# Weather_Shield_V12.net
KiCad netlist of a schematic drawn in EAGLE
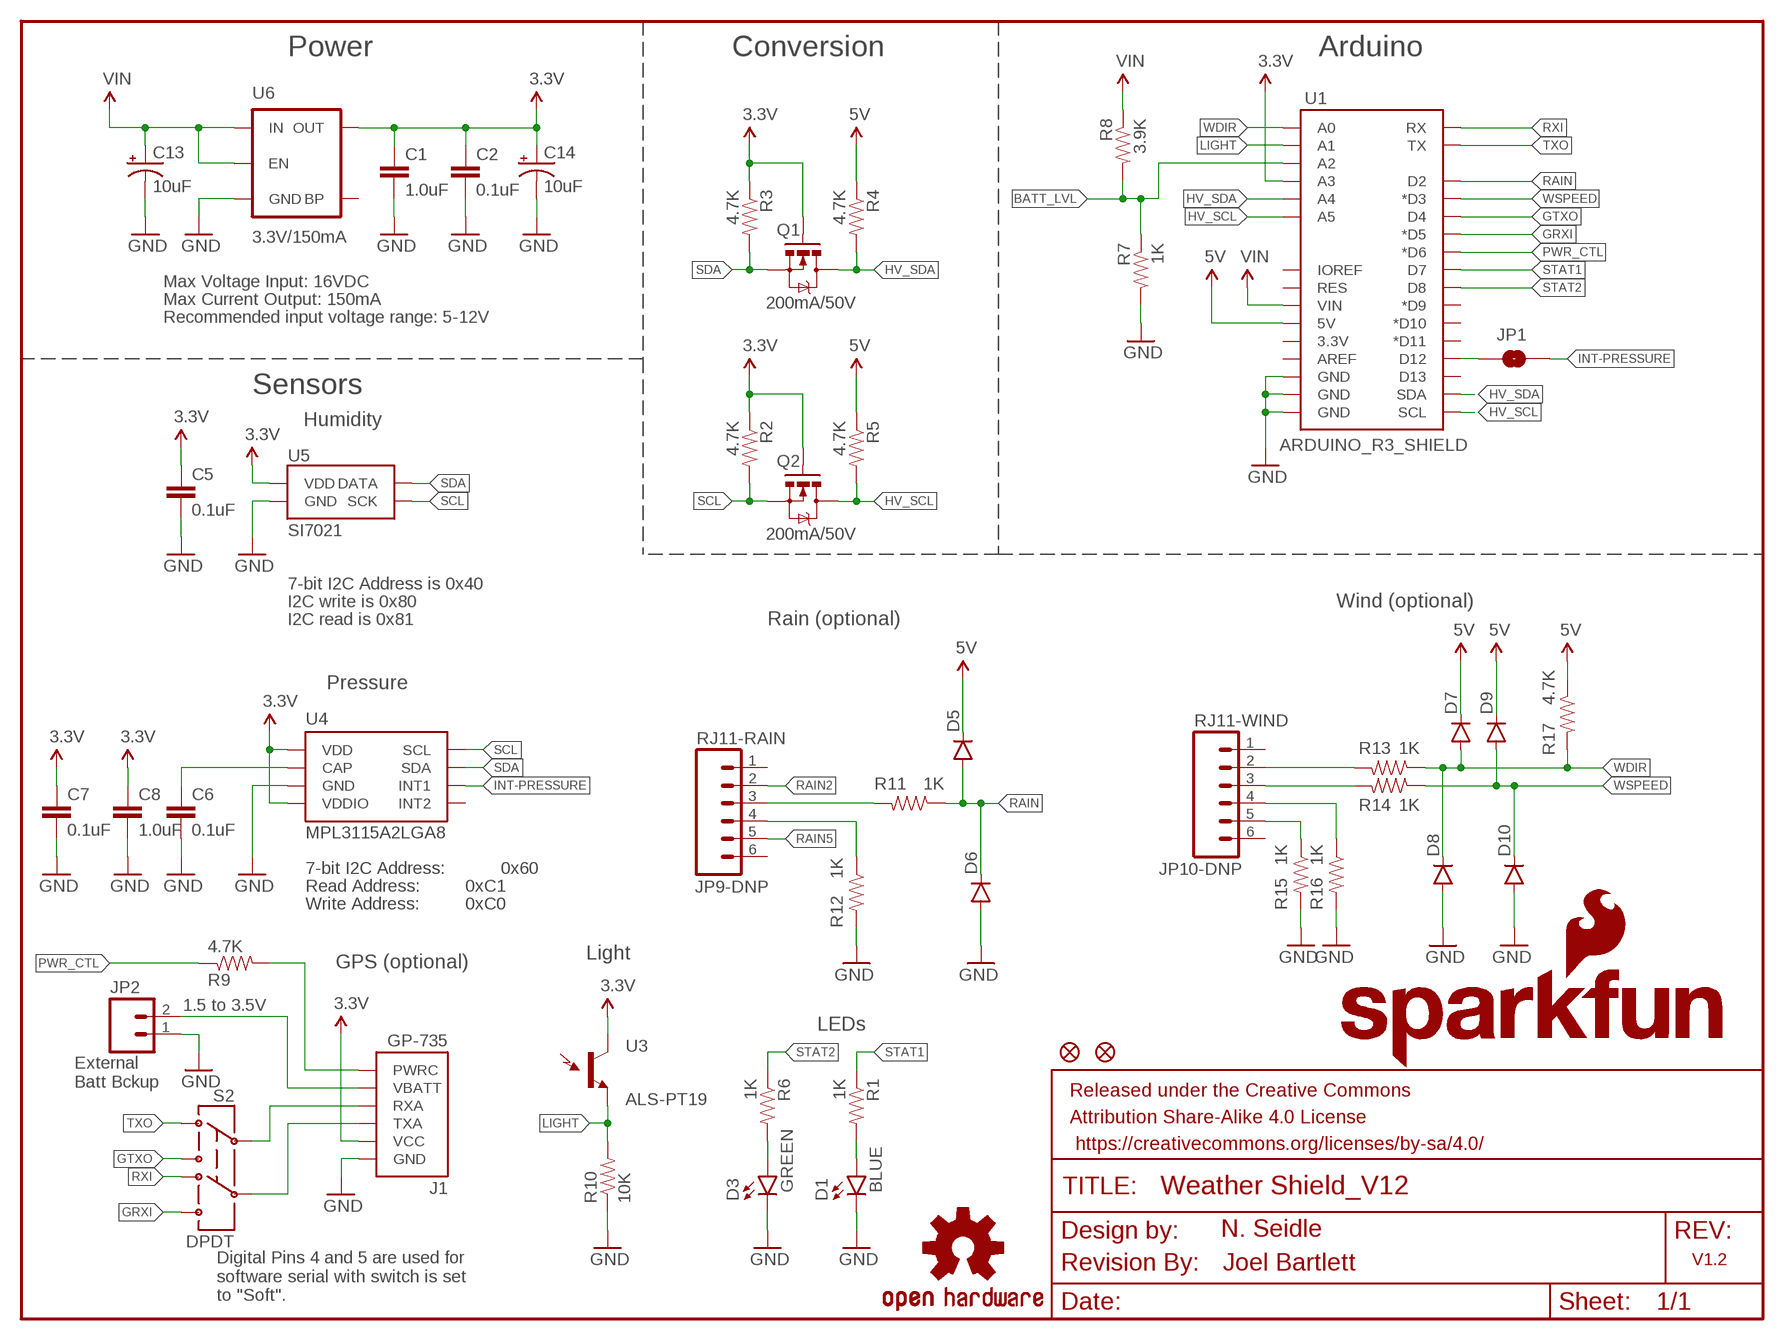
[diagram p0: schematic, sheet 1]

(export (version "E")
  (design (tool "Eeschema 10.0.6"))
  (components
    (comp (ref "C1")
      (value "1.0uF")
      (footprint "eagle-import:0603-CAP")
      (libsource (lib "eagle-import") (part "1.0UF-16V-10%(0603)"))
    )
    (comp (ref "C2")
      (value "0.1uF")
      (footprint "eagle-import:0603-CAP")
      (libsource (lib "eagle-import") (part "0.1UF-25V(+80/-20%)(0603)"))
    )
    (comp (ref "C5")
      (value "0.1uF")
      (footprint "eagle-import:0603-CAP")
      (libsource (lib "eagle-import") (part "0.1UF-25V(+80/-20%)(0603)"))
    )
    (comp (ref "C6")
      (value "0.1uF")
      (footprint "eagle-import:0603-CAP")
      (libsource (lib "eagle-import") (part "0.1UF-25V(+80/-20%)(0603)"))
    )
    (comp (ref "C7")
      (value "0.1uF")
      (footprint "eagle-import:0603-CAP")
      (libsource (lib "eagle-import") (part "0.1UF-25V(+80/-20%)(0603)"))
    )
    (comp (ref "C8")
      (value "1.0uF")
      (footprint "eagle-import:0603-CAP")
      (libsource (lib "eagle-import") (part "1.0UF-16V-10%(0603)"))
    )
    (comp (ref "C13")
      (value "10uF")
      (footprint "eagle-import:EIA3216")
      (libsource (lib "eagle-import") (part "10UF-16V-10%(TANT)"))
    )
    (comp (ref "C14")
      (value "10uF")
      (footprint "eagle-import:EIA3216")
      (libsource (lib "eagle-import") (part "10UF-16V-10%(TANT)"))
    )
    (comp (ref "D1")
      (value "BLUE")
      (footprint "eagle-import:LED-0603")
      (libsource (lib "eagle-import") (part "LED-BLUE0603"))
    )
    (comp (ref "D3")
      (value "GREEN")
      (footprint "eagle-import:LED-0603")
      (libsource (lib "eagle-import") (part "LED-GREEN0603"))
    )
    (comp (ref "D5")
      (value "DIODEBAS16")
      (footprint "eagle-import:SOD-323")
      (libsource (lib "eagle-import") (part "DIODEBAS16"))
    )
    (comp (ref "D6")
      (value "DIODEBAS16")
      (footprint "eagle-import:SOD-323")
      (libsource (lib "eagle-import") (part "DIODEBAS16"))
    )
    (comp (ref "D7")
      (value "DIODEBAS16")
      (footprint "eagle-import:SOD-323")
      (libsource (lib "eagle-import") (part "DIODEBAS16"))
    )
    (comp (ref "D8")
      (value "DIODEBAS16")
      (footprint "eagle-import:SOD-323")
      (libsource (lib "eagle-import") (part "DIODEBAS16"))
    )
    (comp (ref "D9")
      (value "DIODEBAS16")
      (footprint "eagle-import:SOD-323")
      (libsource (lib "eagle-import") (part "DIODEBAS16"))
    )
    (comp (ref "D10")
      (value "DIODEBAS16")
      (footprint "eagle-import:SOD-323")
      (libsource (lib "eagle-import") (part "DIODEBAS16"))
    )
    (comp (ref "FD1")
      (value "FIDUCIAL1X2")
      (footprint "eagle-import:FIDUCIAL-1X2")
      (libsource (lib "eagle-import") (part "FIDUCIAL1X2"))
    )
    (comp (ref "FD2")
      (value "FIDUCIAL1X2")
      (footprint "eagle-import:FIDUCIAL-1X2")
      (libsource (lib "eagle-import") (part "FIDUCIAL1X2"))
    )
    (comp (ref "FRAME1")
      (value "FRAME-LETTER")
      (footprint "eagle-import:CREATIVE_COMMONS")
      (libsource (lib "eagle-import") (part "FRAME-LETTER"))
    )
    (comp (ref "J1")
      (value "GP-735")
      (footprint "eagle-import:GP-635T")
      (libsource (lib "eagle-import") (part "GP-635TSMD"))
    )
    (comp (ref "JP1")
      (value "JUMPER-PAD-2-NO")
      (footprint "eagle-import:PAD-JUMPER-2-NO_NO_SILK")
      (libsource (lib "eagle-import") (part "JUMPER-PAD-2-NO"))
    )
    (comp (ref "JP2")
      (value "External Batt Bckup")
      (footprint "eagle-import:1X02")
      (libsource (lib "eagle-import") (part "M02PTH"))
    )
    (comp (ref "JP9-DNP")
      (value "RJ11-RAIN")
      (footprint "eagle-import:RJ11-6")
      (libsource (lib "eagle-import") (part "RJ11-6PTH"))
    )
    (comp (ref "JP10-DNP")
      (value "RJ11-WIND")
      (footprint "eagle-import:RJ11-6")
      (libsource (lib "eagle-import") (part "RJ11-6PTH"))
    )
    (comp (ref "LOGO1")
      (value "OSHW-LOGOM")
      (footprint "eagle-import:OSHW-LOGO-M")
      (libsource (lib "eagle-import") (part "OSHW-LOGOM"))
    )
    (comp (ref "LOGO2")
      (value "SFE_LOGO_NAME_FLAME.1_INCH")
      (footprint "eagle-import:SFE_LOGO_NAME_FLAME_.1")
      (libsource (lib "eagle-import") (part "SFE_LOGO_NAME_FLAME.1_INCH"))
    )
    (comp (ref "Q1")
      (value "200mA/50V")
      (footprint "eagle-import:SOT23-3")
      (libsource (lib "eagle-import") (part "MOSFET-NCHANNELBSS138"))
    )
    (comp (ref "Q2")
      (value "200mA/50V")
      (footprint "eagle-import:SOT23-3")
      (libsource (lib "eagle-import") (part "MOSFET-NCHANNELBSS138"))
    )
    (comp (ref "R1")
      (value "1K")
      (footprint "eagle-import:0603-RES")
      (libsource (lib "eagle-import") (part "1KOHM-1/10W-1%(0603)"))
    )
    (comp (ref "R2")
      (value "4.7K")
      (footprint "eagle-import:0603-RES")
      (libsource (lib "eagle-import") (part "4.7KOHM-1/10W-1%(0603)"))
    )
    (comp (ref "R3")
      (value "4.7K")
      (footprint "eagle-import:0603-RES")
      (libsource (lib "eagle-import") (part "4.7KOHM-1/10W-1%(0603)"))
    )
    (comp (ref "R4")
      (value "4.7K")
      (footprint "eagle-import:0603-RES")
      (libsource (lib "eagle-import") (part "4.7KOHM-1/10W-1%(0603)"))
    )
    (comp (ref "R5")
      (value "4.7K")
      (footprint "eagle-import:0603-RES")
      (libsource (lib "eagle-import") (part "4.7KOHM-1/10W-1%(0603)"))
    )
    (comp (ref "R6")
      (value "1K")
      (footprint "eagle-import:0603-RES")
      (libsource (lib "eagle-import") (part "1KOHM-1/10W-1%(0603)"))
    )
    (comp (ref "R7")
      (value "1K")
      (footprint "eagle-import:0603-RES")
      (libsource (lib "eagle-import") (part "1KOHM-1/10W-1%(0603)"))
    )
    (comp (ref "R8")
      (value "3.9K")
      (footprint "eagle-import:0603")
      (libsource (lib "eagle-import") (part "3.9KOHM1/10W1%(0603)"))
    )
    (comp (ref "R9")
      (value "4.7K")
      (footprint "eagle-import:0603-RES")
      (libsource (lib "eagle-import") (part "4.7KOHM-1/10W-1%(0603)"))
    )
    (comp (ref "R10")
      (value "10K")
      (footprint "eagle-import:0603-RES")
      (libsource (lib "eagle-import") (part "10KOHM-1/10W-1%(0603)0603"))
    )
    (comp (ref "R11")
      (value "1K")
      (footprint "eagle-import:0603-RES")
      (libsource (lib "eagle-import") (part "1KOHM-1/10W-1%(0603)"))
    )
    (comp (ref "R12")
      (value "1K")
      (footprint "eagle-import:0603-RES")
      (libsource (lib "eagle-import") (part "1KOHM-1/10W-1%(0603)"))
    )
    (comp (ref "R13")
      (value "1K")
      (footprint "eagle-import:0603-RES")
      (libsource (lib "eagle-import") (part "1KOHM-1/10W-1%(0603)"))
    )
    (comp (ref "R14")
      (value "1K")
      (footprint "eagle-import:0603-RES")
      (libsource (lib "eagle-import") (part "1KOHM-1/10W-1%(0603)"))
    )
    (comp (ref "R15")
      (value "1K")
      (footprint "eagle-import:0603-RES")
      (libsource (lib "eagle-import") (part "1KOHM-1/10W-1%(0603)"))
    )
    (comp (ref "R16")
      (value "1K")
      (footprint "eagle-import:0603-RES")
      (libsource (lib "eagle-import") (part "1KOHM-1/10W-1%(0603)"))
    )
    (comp (ref "R17")
      (value "4.7K")
      (footprint "eagle-import:0603-RES")
      (libsource (lib "eagle-import") (part "4.7KOHM-1/10W-1%(0603)"))
    )
    (comp (ref "S2")
      (value "DPDT")
      (footprint "eagle-import:AYZ0202")
      (libsource (lib "eagle-import") (part "SWITCH-DPDTAYZ0202"))
    )
    (comp (ref "U$2")
      (value "REVISION")
      (footprint "eagle-import:REVISION")
      (libsource (lib "eagle-import") (part "REVISION"))
    )
    (comp (ref "U1")
      (value "ARDUINO_R3_SHIELD")
      (footprint "eagle-import:UNO_R3_SHIELD")
      (libsource (lib "eagle-import") (part "ARDUINO_R3_SHIELD"))
    )
    (comp (ref "U3")
      (value "ALS-PT19")
      (footprint "eagle-import:ALS-PT19")
      (libsource (lib "eagle-import") (part "LIGHTSENSORALS"))
    )
    (comp (ref "U4")
      (value "MPL3115A2LGA8")
      (footprint "eagle-import:LGA8")
      (libsource (lib "eagle-import") (part "MPL3115A2LGA8"))
    )
    (comp (ref "U5")
      (value "SI7021")
      (footprint "eagle-import:SI7021")
      (libsource (lib "eagle-import") (part "SI7021"))
    )
    (comp (ref "U6")
      (value "3.3V/150mA")
      (footprint "eagle-import:SOT23-5")
      (libsource (lib "eagle-import") (part "V_REG_MIC52053.3V"))
    )
  )
  (nets
    (net (code "1") (name "3.3V") (class "Default")
      (node (ref "C1") (pin "1") (pinfunction "1_1") (pintype "passive"))
      (node (ref "C14") (pin "A") (pinfunction "+_A") (pintype "passive"))
      (node (ref "C2") (pin "1") (pinfunction "1_1") (pintype "passive"))
      (node (ref "C5") (pin "1") (pinfunction "1_1") (pintype "passive"))
      (node (ref "C7") (pin "1") (pinfunction "1_1") (pintype "passive"))
      (node (ref "C8") (pin "1") (pinfunction "1_1") (pintype "passive"))
      (node (ref "J1") (pin "2") (pinfunction "VCC_2") (pintype "power_in"))
      (node (ref "Q1") (pin "1") (pinfunction "G_1") (pintype "passive"))
      (node (ref "Q2") (pin "1") (pinfunction "G_1") (pintype "passive"))
      (node (ref "R2") (pin "1") (pinfunction "1_1") (pintype "passive"))
      (node (ref "R3") (pin "1") (pinfunction "1_1") (pintype "passive"))
      (node (ref "U1") (pin "A3") (pinfunction "A3_A3") (pintype "bidirectional"))
      (node (ref "U3") (pin "C") (pinfunction "C1_C") (pintype "passive"))
      (node (ref "U4") (pin "1") (pinfunction "VDD_1") (pintype "power_in"))
      (node (ref "U4") (pin "4") (pinfunction "VDDIO_4") (pintype "power_in"))
      (node (ref "U5") (pin "VDD") (pinfunction "VDD_VDD") (pintype "power_in"))
      (node (ref "U6") (pin "5") (pinfunction "OUT_5") (pintype "passive"))
    )
    (net (code "2") (name "5V") (class "Default")
      (node (ref "D5") (pin "C") (pinfunction "C_C") (pintype "passive"))
      (node (ref "D7") (pin "C") (pinfunction "C_C") (pintype "passive"))
      (node (ref "D9") (pin "C") (pinfunction "C_C") (pintype "passive"))
      (node (ref "R17") (pin "1") (pinfunction "1_1") (pintype "passive"))
      (node (ref "R4") (pin "1") (pinfunction "1_1") (pintype "passive"))
      (node (ref "R5") (pin "1") (pinfunction "1_1") (pintype "passive"))
      (node (ref "U1") (pin "5V") (pinfunction "5V_5V") (pintype "bidirectional"))
    )
    (net (code "3") (name "BATT_LVL") (class "Default")
      (node (ref "R7") (pin "1") (pinfunction "1_1") (pintype "passive"))
      (node (ref "R8") (pin "2") (pinfunction "2_2") (pintype "passive"))
      (node (ref "U1") (pin "A2") (pinfunction "A2_A2") (pintype "bidirectional"))
    )
    (net (code "4") (name "GND") (class "Default")
      (node (ref "C1") (pin "2") (pinfunction "2_2") (pintype "passive"))
      (node (ref "C13") (pin "C") (pinfunction "-_C") (pintype "passive"))
      (node (ref "C14") (pin "C") (pinfunction "-_C") (pintype "passive"))
      (node (ref "C2") (pin "2") (pinfunction "2_2") (pintype "passive"))
      (node (ref "C5") (pin "2") (pinfunction "2_2") (pintype "passive"))
      (node (ref "C6") (pin "2") (pinfunction "2_2") (pintype "passive"))
      (node (ref "C7") (pin "2") (pinfunction "2_2") (pintype "passive"))
      (node (ref "C8") (pin "2") (pinfunction "2_2") (pintype "passive"))
      (node (ref "D1") (pin "C") (pinfunction "C_C") (pintype "passive"))
      (node (ref "D10") (pin "A") (pinfunction "A_A") (pintype "passive"))
      (node (ref "D3") (pin "C") (pinfunction "C_C") (pintype "passive"))
      (node (ref "D6") (pin "A") (pinfunction "A_A") (pintype "passive"))
      (node (ref "D8") (pin "A") (pinfunction "A_A") (pintype "passive"))
      (node (ref "J1") (pin "1") (pinfunction "GND_1") (pintype "power_in"))
      (node (ref "JP2") (pin "1") (pinfunction "1_1") (pintype "passive"))
      (node (ref "R10") (pin "1") (pinfunction "1_1") (pintype "passive"))
      (node (ref "R12") (pin "2") (pinfunction "2_2") (pintype "passive"))
      (node (ref "R15") (pin "2") (pinfunction "2_2") (pintype "passive"))
      (node (ref "R16") (pin "2") (pinfunction "2_2") (pintype "passive"))
      (node (ref "R7") (pin "2") (pinfunction "2_2") (pintype "passive"))
      (node (ref "U1") (pin "GND@0") (pinfunction "GND_GND@0") (pintype "bidirectional"))
      (node (ref "U1") (pin "GND@1") (pinfunction "GND_GND@1") (pintype "bidirectional"))
      (node (ref "U1") (pin "GND@2") (pinfunction "GND_GND@2") (pintype "bidirectional"))
      (node (ref "U4") (pin "3") (pinfunction "GND_3") (pintype "power_in"))
      (node (ref "U5") (pin "GND") (pinfunction "GND_GND") (pintype "power_in"))
      (node (ref "U6") (pin "2") (pinfunction "GND_2") (pintype "input"))
    )
    (net (code "5") (name "GRXI") (class "Default")
      (node (ref "S2") (pin "6") (pinfunction "6_6") (pintype "bidirectional"))
      (node (ref "U1") (pin "D5") (pinfunction "*D5_D5") (pintype "bidirectional"))
    )
    (net (code "6") (name "GTXO") (class "Default")
      (node (ref "S2") (pin "3") (pinfunction "3_3") (pintype "bidirectional"))
      (node (ref "U1") (pin "D4") (pinfunction "D4_D4") (pintype "bidirectional"))
    )
    (net (code "7") (name "HV_SCL") (class "Default")
      (node (ref "Q2") (pin "3") (pinfunction "D_3") (pintype "passive"))
      (node (ref "R5") (pin "2") (pinfunction "2_2") (pintype "passive"))
      (node (ref "U1") (pin "A5") (pinfunction "A5_A5") (pintype "bidirectional"))
      (node (ref "U1") (pin "SCL") (pinfunction "SCL_SCL") (pintype "bidirectional"))
    )
    (net (code "8") (name "HV_SDA") (class "Default")
      (node (ref "Q1") (pin "3") (pinfunction "D_3") (pintype "passive"))
      (node (ref "R4") (pin "2") (pinfunction "2_2") (pintype "passive"))
      (node (ref "U1") (pin "A4") (pinfunction "A4_A4") (pintype "bidirectional"))
      (node (ref "U1") (pin "SDA") (pinfunction "SDA_SDA") (pintype "bidirectional"))
    )
    (net (code "9") (name "INT-PRESSURE") (class "Default")
      (node (ref "JP1") (pin "2") (pinfunction "2_2") (pintype "passive"))
      (node (ref "U4") (pin "6") (pinfunction "INT1_6") (pintype "output"))
    )
    (net (code "10") (name "LIGHT") (class "Default")
      (node (ref "R10") (pin "2") (pinfunction "2_2") (pintype "passive"))
      (node (ref "U1") (pin "A1") (pinfunction "A1_A1") (pintype "bidirectional"))
      (node (ref "U3") (pin "E") (pinfunction "E1_E") (pintype "passive"))
    )
    (net (code "11") (name "Net-(D1-PadA)") (class "Default")
      (node (ref "D1") (pin "A") (pinfunction "A_A") (pintype "passive"))
      (node (ref "R1") (pin "2") (pinfunction "2_2") (pintype "passive"))
    )
    (net (code "12") (name "Net-(D3-PadA)") (class "Default")
      (node (ref "D3") (pin "A") (pinfunction "A_A") (pintype "passive"))
      (node (ref "R6") (pin "2") (pinfunction "2_2") (pintype "passive"))
    )
    (net (code "13") (name "Net-(J1-PWRC)") (class "Default")
      (node (ref "J1") (pin "6") (pinfunction "PWRC_6") (pintype "input"))
      (node (ref "R9") (pin "2") (pinfunction "2_2") (pintype "passive"))
    )
    (net (code "14") (name "Net-(J1-RXA)") (class "Default")
      (node (ref "J1") (pin "4") (pinfunction "RXA_4") (pintype "input"))
      (node (ref "S2") (pin "2") (pinfunction "2_2") (pintype "bidirectional"))
    )
    (net (code "15") (name "Net-(J1-TXA)") (class "Default")
      (node (ref "J1") (pin "3") (pinfunction "TXA_3") (pintype "output"))
      (node (ref "S2") (pin "5") (pinfunction "5_5") (pintype "bidirectional"))
    )
    (net (code "16") (name "Net-(J1-VBATT)") (class "Default")
      (node (ref "J1") (pin "5") (pinfunction "VBATT_5") (pintype "power_in"))
      (node (ref "JP2") (pin "2") (pinfunction "2_2") (pintype "passive"))
    )
    (net (code "17") (name "Net-(JP1-Pad1)") (class "Default")
      (node (ref "JP1") (pin "1") (pinfunction "1_1") (pintype "passive"))
      (node (ref "U1") (pin "D12") (pinfunction "D12_D12") (pintype "bidirectional"))
    )
    (net (code "18") (name "Net-(JP9-DNP-Pad3)") (class "Default")
      (node (ref "JP9-DNP") (pin "3") (pinfunction "3_3") (pintype "passive"))
      (node (ref "R11") (pin "2") (pinfunction "2_2") (pintype "passive"))
    )
    (net (code "19") (name "Net-(JP9-DNP-Pad4)") (class "Default")
      (node (ref "JP9-DNP") (pin "4") (pinfunction "4_4") (pintype "passive"))
      (node (ref "R12") (pin "1") (pinfunction "1_1") (pintype "passive"))
    )
    (net (code "20") (name "Net-(JP10-DNP-Pad2)") (class "Default")
      (node (ref "JP10-DNP") (pin "2") (pinfunction "2_2") (pintype "passive"))
      (node (ref "R13") (pin "2") (pinfunction "2_2") (pintype "passive"))
    )
    (net (code "21") (name "Net-(JP10-DNP-Pad3)") (class "Default")
      (node (ref "JP10-DNP") (pin "3") (pinfunction "3_3") (pintype "passive"))
      (node (ref "R14") (pin "2") (pinfunction "2_2") (pintype "passive"))
    )
    (net (code "22") (name "Net-(JP10-DNP-Pad4)") (class "Default")
      (node (ref "JP10-DNP") (pin "4") (pinfunction "4_4") (pintype "passive"))
      (node (ref "R16") (pin "1") (pinfunction "1_1") (pintype "passive"))
    )
    (net (code "23") (name "Net-(JP10-DNP-Pad5)") (class "Default")
      (node (ref "JP10-DNP") (pin "5") (pinfunction "5_5") (pintype "passive"))
      (node (ref "R15") (pin "1") (pinfunction "1_1") (pintype "passive"))
    )
    (net (code "24") (name "Net-(U4-CAP)") (class "Default")
      (node (ref "C6") (pin "1") (pinfunction "1_1") (pintype "passive"))
      (node (ref "U4") (pin "2") (pinfunction "CAP_2") (pintype "power_in"))
    )
    (net (code "25") (name "PWR_CTL") (class "Default")
      (node (ref "R9") (pin "1") (pinfunction "1_1") (pintype "passive"))
      (node (ref "U1") (pin "D6") (pinfunction "*D6_D6") (pintype "bidirectional"))
    )
    (net (code "26") (name "RAIN") (class "Default")
      (node (ref "D5") (pin "A") (pinfunction "A_A") (pintype "passive"))
      (node (ref "D6") (pin "C") (pinfunction "C_C") (pintype "passive"))
      (node (ref "R11") (pin "1") (pinfunction "1_1") (pintype "passive"))
      (node (ref "U1") (pin "D2") (pinfunction "D2_D2") (pintype "bidirectional"))
    )
    (net (code "27") (name "RAIN2") (class "Default")
      (node (ref "JP9-DNP") (pin "2") (pinfunction "2_2") (pintype "passive"))
    )
    (net (code "28") (name "RAIN5") (class "Default")
      (node (ref "JP9-DNP") (pin "5") (pinfunction "5_5") (pintype "passive"))
    )
    (net (code "29") (name "RXI") (class "Default")
      (node (ref "S2") (pin "4") (pinfunction "4_4") (pintype "bidirectional"))
      (node (ref "U1") (pin "RX") (pinfunction "RX_RX") (pintype "bidirectional"))
    )
    (net (code "30") (name "SCL") (class "Default")
      (node (ref "Q2") (pin "2") (pinfunction "S_2") (pintype "passive"))
      (node (ref "R2") (pin "2") (pinfunction "2_2") (pintype "passive"))
      (node (ref "U4") (pin "8") (pinfunction "SCL_8") (pintype "bidirectional"))
      (node (ref "U5") (pin "SCK") (pinfunction "SCK_SCK") (pintype "input"))
    )
    (net (code "31") (name "SDA") (class "Default")
      (node (ref "Q1") (pin "2") (pinfunction "S_2") (pintype "passive"))
      (node (ref "R3") (pin "2") (pinfunction "2_2") (pintype "passive"))
      (node (ref "U4") (pin "7") (pinfunction "SDA_7") (pintype "bidirectional"))
      (node (ref "U5") (pin "DATA") (pinfunction "DATA_DATA") (pintype "bidirectional"))
    )
    (net (code "32") (name "STAT1") (class "Default")
      (node (ref "R1") (pin "1") (pinfunction "1_1") (pintype "passive"))
      (node (ref "U1") (pin "D7") (pinfunction "D7_D7") (pintype "bidirectional"))
    )
    (net (code "33") (name "STAT2") (class "Default")
      (node (ref "R6") (pin "1") (pinfunction "1_1") (pintype "passive"))
      (node (ref "U1") (pin "D8") (pinfunction "D8_D8") (pintype "bidirectional"))
    )
    (net (code "34") (name "TXO") (class "Default")
      (node (ref "S2") (pin "1") (pinfunction "1_1") (pintype "bidirectional"))
      (node (ref "U1") (pin "TX") (pinfunction "TX_TX") (pintype "bidirectional"))
    )
    (net (code "35") (name "VIN") (class "Default")
      (node (ref "C13") (pin "A") (pinfunction "+_A") (pintype "passive"))
      (node (ref "R8") (pin "1") (pinfunction "1_1") (pintype "passive"))
      (node (ref "U1") (pin "VIN") (pinfunction "VIN_VIN") (pintype "bidirectional"))
      (node (ref "U6") (pin "1") (pinfunction "IN_1") (pintype "input"))
      (node (ref "U6") (pin "3") (pinfunction "EN_3") (pintype "input"))
    )
    (net (code "36") (name "WDIR") (class "Default")
      (node (ref "D7") (pin "A") (pinfunction "A_A") (pintype "passive"))
      (node (ref "D8") (pin "C") (pinfunction "C_C") (pintype "passive"))
      (node (ref "R13") (pin "1") (pinfunction "1_1") (pintype "passive"))
      (node (ref "R17") (pin "2") (pinfunction "2_2") (pintype "passive"))
      (node (ref "U1") (pin "A0") (pinfunction "A0_A0") (pintype "bidirectional"))
    )
    (net (code "37") (name "WSPEED") (class "Default")
      (node (ref "D10") (pin "C") (pinfunction "C_C") (pintype "passive"))
      (node (ref "D9") (pin "A") (pinfunction "A_A") (pintype "passive"))
      (node (ref "R14") (pin "1") (pinfunction "1_1") (pintype "passive"))
      (node (ref "U1") (pin "D3") (pinfunction "*D3_D3") (pintype "bidirectional"))
    )
    (net (code "38") (name "unconnected-(JP9-DNP-Pad1)") (class "Default")
      (node (ref "JP9-DNP") (pin "1") (pinfunction "1_1") (pintype "passive"))
    )
    (net (code "39") (name "unconnected-(JP9-DNP-Pad6)") (class "Default")
      (node (ref "JP9-DNP") (pin "6") (pinfunction "6_6") (pintype "passive"))
    )
    (net (code "40") (name "unconnected-(JP10-DNP-Pad1)") (class "Default")
      (node (ref "JP10-DNP") (pin "1") (pinfunction "1_1") (pintype "passive"))
    )
    (net (code "41") (name "unconnected-(JP10-DNP-Pad6)") (class "Default")
      (node (ref "JP10-DNP") (pin "6") (pinfunction "6_6") (pintype "passive"))
    )
    (net (code "42") (name "unconnected-(U1-*D9-PadD9)") (class "Default")
      (node (ref "U1") (pin "D9") (pinfunction "*D9_D9") (pintype "bidirectional"))
    )
    (net (code "43") (name "unconnected-(U1-*D10-PadD10)") (class "Default")
      (node (ref "U1") (pin "D10") (pinfunction "*D10_D10") (pintype "bidirectional"))
    )
    (net (code "44") (name "unconnected-(U1-*D11-PadD11)") (class "Default")
      (node (ref "U1") (pin "D11") (pinfunction "*D11_D11") (pintype "bidirectional"))
    )
    (net (code "45") (name "unconnected-(U1-Pad3.3V)") (class "Default")
      (node (ref "U1") (pin "3.3V") (pinfunction "3.3V_3.3V") (pintype "bidirectional"))
    )
    (net (code "46") (name "unconnected-(U1-PadAREF)") (class "Default")
      (node (ref "U1") (pin "AREF") (pinfunction "AREF_AREF") (pintype "bidirectional"))
    )
    (net (code "47") (name "unconnected-(U1-PadD13)") (class "Default")
      (node (ref "U1") (pin "D13") (pinfunction "D13_D13") (pintype "bidirectional"))
    )
    (net (code "48") (name "unconnected-(U1-PadIOREF)") (class "Default")
      (node (ref "U1") (pin "IOREF") (pinfunction "IOREF_IOREF") (pintype "bidirectional"))
    )
    (net (code "49") (name "unconnected-(U1-PadRES)") (class "Default")
      (node (ref "U1") (pin "RES") (pinfunction "RES_RES") (pintype "bidirectional"))
    )
    (net (code "50") (name "unconnected-(U4-INT2-Pad5)") (class "Default")
      (node (ref "U4") (pin "5") (pinfunction "INT2_5") (pintype "output"))
    )
    (net (code "51") (name "unconnected-(U6-BP-Pad4)") (class "Default")
      (node (ref "U6") (pin "4") (pinfunction "BP_4") (pintype "input"))
    )
  )
)
